# digAudio-rcj-tg10da1nslf.net
KiCad netlist of a schematic drawn in EAGLE
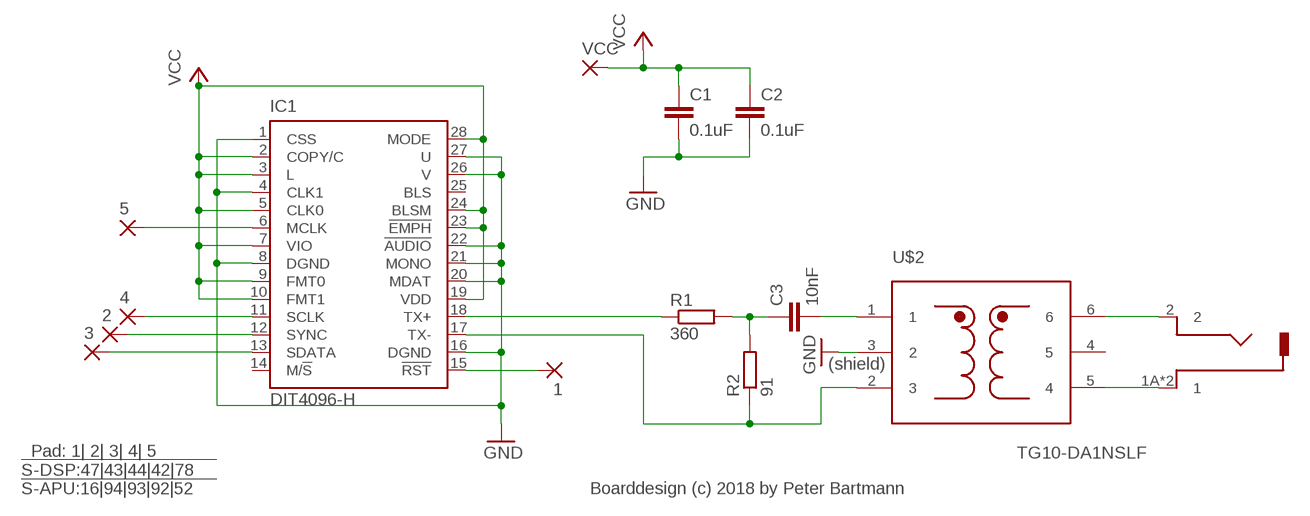
[diagram p0: schematic, sheet 1]

(export (version "E")
  (design (tool "Eeschema 10.0.6"))
  (components
    (comp (ref "1")
      (value "SMD1")
      (footprint "eagle-import:SMD0,8-1,6")
      (libsource (lib "eagle-import") (part "SMD1"))
    )
    (comp (ref "2")
      (value "SMD1")
      (footprint "eagle-import:SMD0,8-1,6")
      (libsource (lib "eagle-import") (part "SMD1"))
    )
    (comp (ref "3")
      (value "SMD1")
      (footprint "eagle-import:SMD0,8-1,6")
      (libsource (lib "eagle-import") (part "SMD1"))
    )
    (comp (ref "4")
      (value "SMD1")
      (footprint "eagle-import:SMD0,8-1,6")
      (libsource (lib "eagle-import") (part "SMD1"))
    )
    (comp (ref "5")
      (value "SMD1")
      (footprint "eagle-import:SMD0,8-1,6")
      (libsource (lib "eagle-import") (part "SMD1"))
    )
    (comp (ref "C1")
      (value "0.1uF")
      (footprint "eagle-import:C0603")
      (libsource (lib "eagle-import") (part "C-EUC0603"))
    )
    (comp (ref "C2")
      (value "0.1uF")
      (footprint "eagle-import:C0603")
      (libsource (lib "eagle-import") (part "C-EUC0603"))
    )
    (comp (ref "C3")
      (value "10nF")
      (footprint "eagle-import:C0603")
      (libsource (lib "eagle-import") (part "C-EUC0603"))
    )
    (comp (ref "IC1")
      (value "DIT4096-H")
      (footprint "eagle-import:PW_R-PDSO-G28")
      (fields (field (name "MF") "TEXAS INSTRUMENTS") (field (name "MPN") "DIT4192IPW"))
      (libsource (lib "eagle-import") (part "DIT4192-H"))
    )
    (comp (ref "R1")
      (value "360")
      (footprint "eagle-import:R0603")
      (libsource (lib "eagle-import") (part "R-EU_R0603"))
    )
    (comp (ref "R2")
      (value "91")
      (footprint "eagle-import:R0603")
      (libsource (lib "eagle-import") (part "R-EU_R0603"))
    )
    (comp (ref "U$1")
      (value "RCJ-013-SMT-TR")
      (footprint "eagle-import:RCJ_01X_SMT_MODIFIED")
      (libsource (lib "eagle-import") (part "RCJ_01X_SMT-MODIFIED"))
    )
    (comp (ref "U$2")
      (value "TG10-DA1NSLF")
      (footprint "eagle-import:TG10-DA1NSFL")
      (libsource (lib "eagle-import") (part "TG10-DA1NSLF"))
    )
    (comp (ref "VCC")
      (value "SMD2")
      (footprint "eagle-import:SMD1,27-2,54")
      (libsource (lib "eagle-import") (part "SMD2"))
    )
  )
  (nets
    (net (code "1") (name "GND") (class "Default")
      (node (ref "C1") (pin "2") (pinfunction "2_2") (pintype "passive"))
      (node (ref "C2") (pin "2") (pinfunction "2_2") (pintype "passive"))
      (node (ref "IC1") (pin "1") (pinfunction "CSS_1") (pintype "input"))
      (node (ref "IC1") (pin "16") (pinfunction "DGND_16") (pintype "power_in"))
      (node (ref "IC1") (pin "20") (pinfunction "MDAT_20") (pintype "input"))
      (node (ref "IC1") (pin "21") (pinfunction "MONO_21") (pintype "input"))
      (node (ref "IC1") (pin "22") (pinfunction "~{AUDIO}_22") (pintype "input"))
      (node (ref "IC1") (pin "26") (pinfunction "V_26") (pintype "input"))
      (node (ref "IC1") (pin "27") (pinfunction "U_27") (pintype "input"))
      (node (ref "IC1") (pin "4") (pinfunction "CLK1_4") (pintype "input"))
      (node (ref "IC1") (pin "8") (pinfunction "DGND_8") (pintype "power_in"))
      (node (ref "U$2") (pin "3") (pinfunction "2_3") (pintype "bidirectional"))
    )
    (net (code "2") (name "Net-(1-P)") (class "Default")
      (node (ref "1") (pin "P$1") (pinfunction "P_P$1") (pintype "passive"))
      (node (ref "IC1") (pin "15") (pinfunction "~{RST}_15") (pintype "input"))
    )
    (net (code "3") (name "Net-(2-P)") (class "Default")
      (node (ref "2") (pin "P$1") (pinfunction "P_P$1") (pintype "passive"))
      (node (ref "IC1") (pin "12") (pinfunction "SYNC_12") (pintype "bidirectional"))
    )
    (net (code "4") (name "Net-(3-P)") (class "Default")
      (node (ref "3") (pin "P$1") (pinfunction "P_P$1") (pintype "passive"))
      (node (ref "IC1") (pin "13") (pinfunction "SDATA_13") (pintype "input"))
    )
    (net (code "5") (name "Net-(4-P)") (class "Default")
      (node (ref "4") (pin "P$1") (pinfunction "P_P$1") (pintype "passive"))
      (node (ref "IC1") (pin "11") (pinfunction "SCLK_11") (pintype "bidirectional"))
    )
    (net (code "6") (name "Net-(5-P)") (class "Default")
      (node (ref "5") (pin "P$1") (pinfunction "P_P$1") (pintype "passive"))
      (node (ref "IC1") (pin "6") (pinfunction "MCLK_6") (pintype "input"))
    )
    (net (code "7") (name "Net-(C3-Pad1)") (class "Default")
      (node (ref "C3") (pin "1") (pinfunction "1_1") (pintype "passive"))
      (node (ref "R1") (pin "2") (pinfunction "2_2") (pintype "passive"))
      (node (ref "R2") (pin "2") (pinfunction "2_2") (pintype "passive"))
    )
    (net (code "8") (name "Net-(C3-Pad2)") (class "Default")
      (node (ref "C3") (pin "2") (pinfunction "2_2") (pintype "passive"))
      (node (ref "U$2") (pin "1") (pinfunction "1_1") (pintype "bidirectional"))
    )
    (net (code "9") (name "Net-(IC1-TX+)") (class "Default")
      (node (ref "IC1") (pin "18") (pinfunction "TX+_18") (pintype "output"))
      (node (ref "R1") (pin "1") (pinfunction "1_1") (pintype "passive"))
    )
    (net (code "10") (name "Net-(IC1-TX-)") (class "Default")
      (node (ref "IC1") (pin "17") (pinfunction "TX-_17") (pintype "output"))
      (node (ref "R2") (pin "1") (pinfunction "1_1") (pintype "passive"))
      (node (ref "U$2") (pin "2") (pinfunction "3_2") (pintype "bidirectional"))
    )
    (net (code "11") (name "Net-(U$1-Pad2)") (class "Default")
      (node (ref "U$1") (pin "2") (pinfunction "2_2") (pintype "bidirectional"))
      (node (ref "U$2") (pin "6") (pinfunction "6_6") (pintype "bidirectional"))
    )
    (net (code "12") (name "Net-(U$2-4)") (class "Default")
      (node (ref "U$1") (pin "1A") (pinfunction "1_1A") (pintype "bidirectional"))
      (node (ref "U$1") (pin "1B") (pinfunction "1_1B") (pintype "bidirectional"))
      (node (ref "U$2") (pin "5") (pinfunction "4_5") (pintype "bidirectional"))
    )
    (net (code "13") (name "VCC") (class "Default")
      (node (ref "C1") (pin "1") (pinfunction "1_1") (pintype "passive"))
      (node (ref "C2") (pin "1") (pinfunction "1_1") (pintype "passive"))
      (node (ref "IC1") (pin "10") (pinfunction "FMT1_10") (pintype "input"))
      (node (ref "IC1") (pin "19") (pinfunction "VDD_19") (pintype "power_in"))
      (node (ref "IC1") (pin "2") (pinfunction "COPY/C_2") (pintype "input"))
      (node (ref "IC1") (pin "23") (pinfunction "~{EMPH}_23") (pintype "input"))
      (node (ref "IC1") (pin "24") (pinfunction "BLSM_24") (pintype "input"))
      (node (ref "IC1") (pin "28") (pinfunction "MODE_28") (pintype "input"))
      (node (ref "IC1") (pin "3") (pinfunction "L_3") (pintype "input"))
      (node (ref "IC1") (pin "5") (pinfunction "CLK0_5") (pintype "input"))
      (node (ref "IC1") (pin "7") (pinfunction "VIO_7") (pintype "power_in"))
      (node (ref "IC1") (pin "9") (pinfunction "FMT0_9") (pintype "input"))
      (node (ref "VCC") (pin "1") (pinfunction "P_1") (pintype "passive"))
    )
    (net (code "14") (name "unconnected-(IC1-BLS-Pad25)") (class "Default")
      (node (ref "IC1") (pin "25") (pinfunction "BLS_25") (pintype "bidirectional"))
    )
    (net (code "15") (name "unconnected-(IC1-M{slash}~{S}-Pad14)") (class "Default")
      (node (ref "IC1") (pin "14") (pinfunction "M/~{S}_14") (pintype "input"))
    )
    (net (code "16") (name "unconnected-(U$2-5-Pad4)") (class "Default")
      (node (ref "U$2") (pin "4") (pinfunction "5_4") (pintype "bidirectional"))
    )
  )
)
